# ADC.net
KiCad netlist of a schematic drawn in Altium Designer
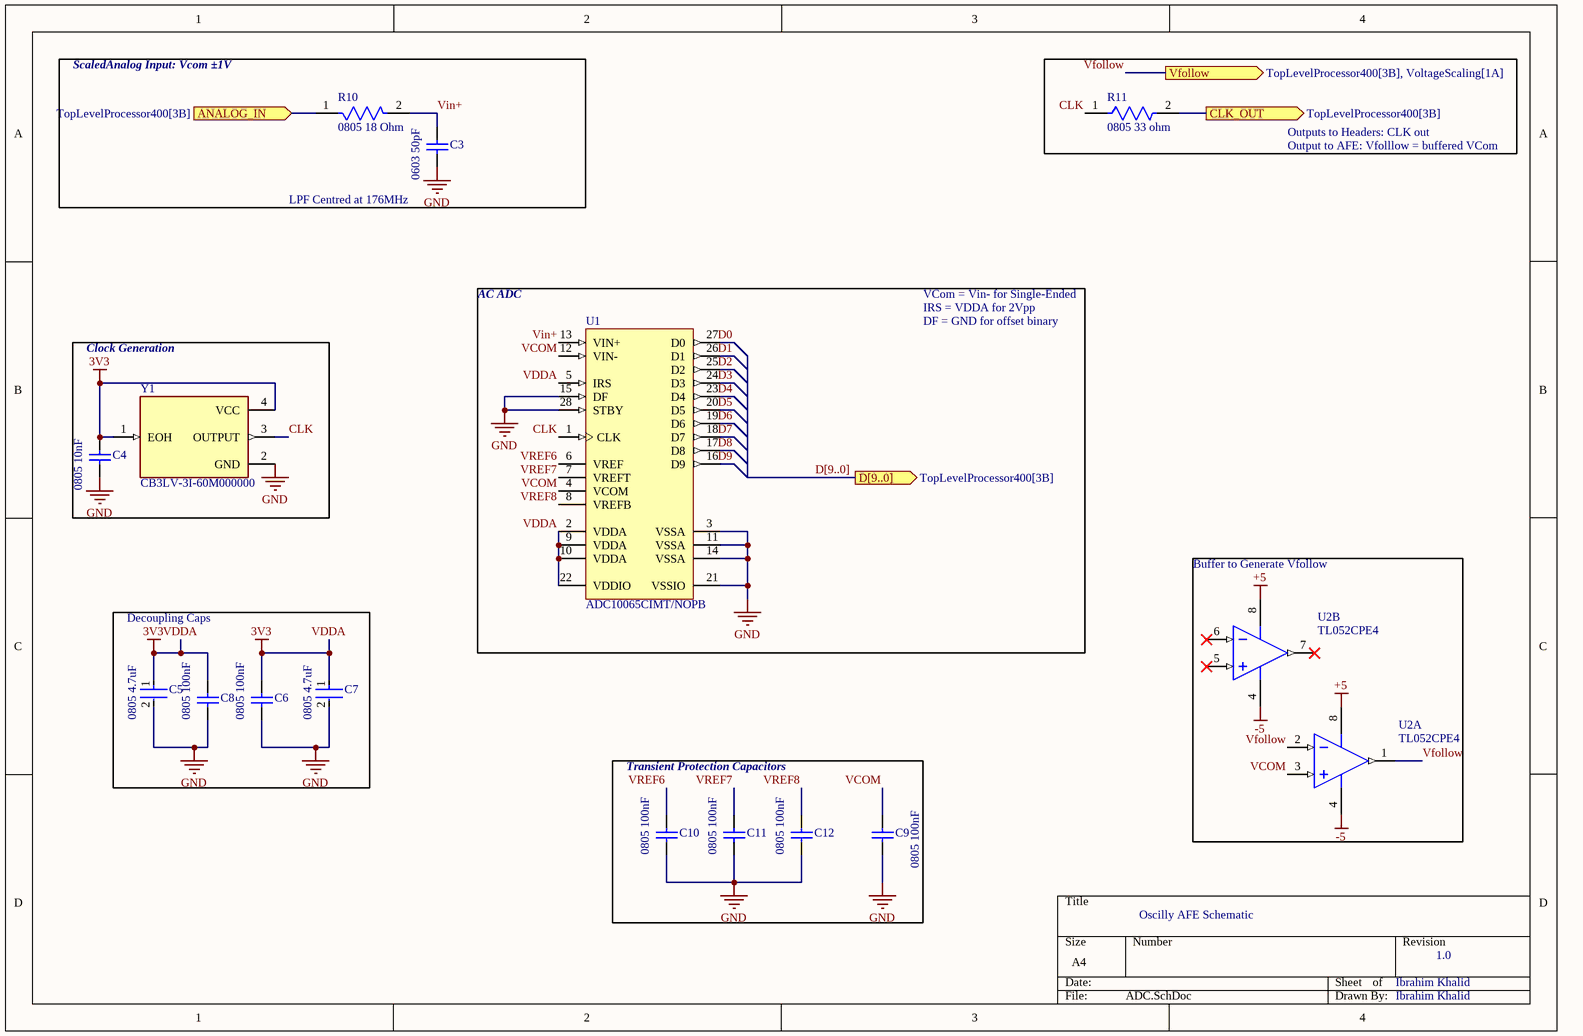
[diagram p0: ADC.SchDoc]

(export (version "E")
  (design (tool "Eeschema 10.0.6"))
  (components
    (comp (ref "C3")
      (value "0603 50pF")
      (footprint "CAPC1608X90X35ML15T15")
      (description "06035A500JAT2A")
      (fields (field (name "MANUFACTURER") "AVX Interconnect / Elco"))
      (libsource (lib "Altium Content Vault") (part "CAP"))
    )
    (comp (ref "C4")
      (value "0805 10nF")
      (footprint "CAPC0805(2012)100_M")
      (description "CAP 10nF 200V ±20% 0805 (2012 Metric) Thickness 1mm SMD")
      (fields (field (name "TOLERANCE") "Â±20%"))
      (libsource (lib "Altium Content Vault") (part "CAP"))
    )
    (comp (ref "C5")
      (value "0805 4.7uF")
      (footprint "FP-CC0805-0_85-MFG")
      (description "CAP CER 4.7UF 16V X7R 0805   CC0805KKX7R7BB475")
      (fields
        (field (name "MANUFACTURER") "Yageo")
        (field (name "OCTOPART") "https://octopart.com/cc0805kkx7r7bb475-yageo-34429188")
      )
      (libsource (lib "Altium Content Vault") (part "11868f565c42a9108669ba33697ecf6"))
    )
    (comp (ref "C6")
      (value "0805 100nF")
      (footprint "CAPC2013X140X50ML20T25")
      (description "0805DD104KAT2A")
      (fields (field (name "MANUFACTURER") "AVX Interconnect / Elco"))
      (libsource (lib "Altium Content Vault") (part "CAP"))
    )
    (comp (ref "C7")
      (value "0805 4.7uF")
      (footprint "FP-CC0805-0_85-MFG")
      (description "CAP CER 4.7UF 16V X7R 0805   CC0805KKX7R7BB475")
      (fields
        (field (name "MANUFACTURER") "Yageo")
        (field (name "OCTOPART") "https://octopart.com/cc0805kkx7r7bb475-yageo-34429188")
      )
      (libsource (lib "Altium Content Vault") (part "11868f565c42a9108669ba33697ecf6"))
    )
    (comp (ref "C8")
      (value "0805 100nF")
      (footprint "CAPC2013X140X50ML20T25")
      (description "0805DD104KAT2A")
      (fields (field (name "MANUFACTURER") "AVX Interconnect / Elco"))
      (libsource (lib "Altium Content Vault") (part "CAP"))
    )
    (comp (ref "C9")
      (value "0805 100nF")
      (footprint "CAPC2013X140X50ML20T25")
      (description "0805DD104KAT2A")
      (fields (field (name "MANUFACTURER") "AVX Interconnect / Elco"))
      (libsource (lib "Altium Content Vault") (part "CAP"))
    )
    (comp (ref "C10")
      (value "0805 100nF")
      (footprint "CAPC2013X140X50ML20T25")
      (description "0805DD104KAT2A")
      (fields (field (name "MANUFACTURER") "AVX Interconnect / Elco"))
      (libsource (lib "Altium Content Vault") (part "CAP"))
    )
    (comp (ref "C11")
      (value "0805 100nF")
      (footprint "CAPC2013X140X50ML20T25")
      (description "0805DD104KAT2A")
      (fields (field (name "MANUFACTURER") "AVX Interconnect / Elco"))
      (libsource (lib "Altium Content Vault") (part "CAP"))
    )
    (comp (ref "C12")
      (value "0805 100nF")
      (footprint "CAPC2013X140X50ML20T25")
      (description "0805DD104KAT2A")
      (fields (field (name "MANUFACTURER") "AVX Interconnect / Elco"))
      (libsource (lib "Altium Content Vault") (part "CAP"))
    )
    (comp (ref "R10")
      (value "0805 18 Ohm")
      (footprint "FP-CR0805-IPC_B")
      (description "Thick Film Chip Resistors 0805 18Ω 0.125W 5% 200ppm/°C  CR0805-JW-180ELF")
      (fields (field (name "TOLERANCE") "5%"))
      (libsource (lib "Altium Content Vault") (part "1029c3af85768c4190bb7ad29bc67b5"))
    )
    (comp (ref "R11")
      (value "0805 33 ohm")
      (footprint "FP-AC0805-MFG")
      (description "RES SMD 33 OHM 1% 1/8W 0805")
      (fields
        (field (name "OCTOPART") "https://octopart.com/ac0805fr-0733rl-yageo-46503501")
        (field (name "MANUFACTURER") "Yageo")
      )
      (libsource (lib "Altium Content Vault") (part "1029c3af85768c4190bb7ad29bc67b5"))
    )
    (comp (ref "U1")
      (value "ADC10065CIMT/NOPB")
      (footprint "PW0028A_L")
      (description "10-Bit 65 MSPS 3V A/D Converter, 28-pin TSSOP, Pb-Free")
      (fields (field (name "MANUFACTURER") "Texas Instruments"))
      (libsource (lib "Altium Content Vault") (part "CON-ADC-ADC10065CIMT"))
    )
    (comp (ref "U2")
      (value "TL052CPE4")
      (footprint "TI-P8")
      (fields (field (name "MANUFACTURER") "Texas Instruments"))
      (libsource (lib "Altium Content Vault") (part "TI-AMP-D6-2-8_D"))
    )
    (comp (ref "Y1")
      (value "CB3LV-3I-60M000000")
      (footprint "OSC_CB3LV-3I-60M000000")
      (description "60 MHz XO (Standard) HCMOS, TTL Oscillator 3.3V Enable/Disable 4-SMD, No Lead")
      (fields (field (name "MF") "CTS-Frequency Controls"))
      (libsource (lib "Ibrahim Khalid") (part "CB3LV-3I-60M000000"))
    )
  )
  (nets
    (net (code "1") (name "+5") (class "Default")
      (node (ref "U2") (pin "8") (pinfunction "VCC+_8") (pintype "power_in"))
    )
    (net (code "2") (name "-5") (class "Default")
      (node (ref "U2") (pin "4") (pinfunction "VCC-_4") (pintype "power_in"))
    )
    (net (code "3") (name "/ANALOG_IN") (class "Default")
      (node (ref "R10") (pin "1") (pinfunction "1_1") (pintype "passive"))
    )
    (net (code "4") (name "/CLK") (class "Default")
      (node (ref "R11") (pin "1") (pinfunction "1_1") (pintype "passive"))
      (node (ref "U1") (pin "1") (pinfunction "CLK_1") (pintype "input"))
      (node (ref "Y1") (pin "3") (pinfunction "OUTPUT_3") (pintype "output"))
    )
    (net (code "5") (name "/CLK_OUT") (class "Default")
      (node (ref "R11") (pin "2") (pinfunction "2_2") (pintype "passive"))
    )
    (net (code "6") (name "/D0") (class "Default")
      (node (ref "U1") (pin "27") (pinfunction "D0_27") (pintype "output"))
    )
    (net (code "7") (name "/D1") (class "Default")
      (node (ref "U1") (pin "26") (pinfunction "D1_26") (pintype "output"))
    )
    (net (code "8") (name "/D2") (class "Default")
      (node (ref "U1") (pin "25") (pinfunction "D2_25") (pintype "output"))
    )
    (net (code "9") (name "/D3") (class "Default")
      (node (ref "U1") (pin "24") (pinfunction "D3_24") (pintype "output"))
    )
    (net (code "10") (name "/D4") (class "Default")
      (node (ref "U1") (pin "23") (pinfunction "D4_23") (pintype "output"))
    )
    (net (code "11") (name "/D5") (class "Default")
      (node (ref "U1") (pin "20") (pinfunction "D5_20") (pintype "output"))
    )
    (net (code "12") (name "/D6") (class "Default")
      (node (ref "U1") (pin "19") (pinfunction "D6_19") (pintype "output"))
    )
    (net (code "13") (name "/D7") (class "Default")
      (node (ref "U1") (pin "18") (pinfunction "D7_18") (pintype "output"))
    )
    (net (code "14") (name "/D8") (class "Default")
      (node (ref "U1") (pin "17") (pinfunction "D8_17") (pintype "output"))
    )
    (net (code "15") (name "/D9") (class "Default")
      (node (ref "U1") (pin "16") (pinfunction "D9_16") (pintype "output"))
    )
    (net (code "17") (name "/VCOM") (class "Default")
      (node (ref "C9") (pin "1") (pinfunction "1_1") (pintype "passive"))
      (node (ref "U1") (pin "12") (pinfunction "VIN-_12") (pintype "input"))
      (node (ref "U1") (pin "4") (pinfunction "VCOM_4") (pintype "power_in"))
      (node (ref "U2") (pin "3") (pinfunction "IN1+_3") (pintype "input"))
    )
    (net (code "18") (name "/VREF6") (class "Default")
      (node (ref "C10") (pin "1") (pinfunction "1_1") (pintype "passive"))
      (node (ref "U1") (pin "6") (pinfunction "VREF_6") (pintype "power_in"))
    )
    (net (code "19") (name "/VREF7") (class "Default")
      (node (ref "C11") (pin "1") (pinfunction "1_1") (pintype "passive"))
      (node (ref "U1") (pin "7") (pinfunction "VREFT_7") (pintype "power_in"))
    )
    (net (code "20") (name "/VREF8") (class "Default")
      (node (ref "C12") (pin "1") (pinfunction "1_1") (pintype "passive"))
      (node (ref "U1") (pin "8") (pinfunction "VREFB_8") (pintype "power_in"))
    )
    (net (code "21") (name "/Vfollow") (class "Default")
      (node (ref "U2") (pin "1") (pinfunction "OUT1_1") (pintype "output"))
      (node (ref "U2") (pin "2") (pinfunction "IN1-_2") (pintype "input"))
    )
    (net (code "22") (name "/Vin+") (class "Default")
      (node (ref "C3") (pin "1") (pinfunction "1_1") (pintype "passive"))
      (node (ref "R10") (pin "2") (pinfunction "2_2") (pintype "passive"))
      (node (ref "U1") (pin "13") (pinfunction "VIN+_13") (pintype "input"))
    )
    (net (code "23") (name "3V3") (class "Default")
      (node (ref "C4") (pin "1") (pinfunction "1_1") (pintype "passive"))
      (node (ref "C5") (pin "1") (pinfunction "1_1") (pintype "passive"))
      (node (ref "C6") (pin "1") (pinfunction "1_1") (pintype "passive"))
      (node (ref "C7") (pin "1") (pinfunction "1_1") (pintype "passive"))
      (node (ref "C8") (pin "1") (pinfunction "1_1") (pintype "passive"))
      (node (ref "U1") (pin "10") (pinfunction "VDDA_10") (pintype "power_in"))
      (node (ref "U1") (pin "2") (pinfunction "VDDA_2") (pintype "power_in"))
      (node (ref "U1") (pin "22") (pinfunction "VDDIO_22") (pintype "power_in"))
      (node (ref "U1") (pin "5") (pinfunction "IRS_5") (pintype "input"))
      (node (ref "U1") (pin "9") (pinfunction "VDDA_9") (pintype "power_in"))
      (node (ref "Y1") (pin "1") (pinfunction "EOH_1") (pintype "input"))
      (node (ref "Y1") (pin "4") (pinfunction "VCC_4") (pintype "power_in"))
    )
    (net (code "24") (name "GND") (class "Default")
      (node (ref "C10") (pin "2") (pinfunction "2_2") (pintype "passive"))
      (node (ref "C11") (pin "2") (pinfunction "2_2") (pintype "passive"))
      (node (ref "C12") (pin "2") (pinfunction "2_2") (pintype "passive"))
      (node (ref "C3") (pin "2") (pinfunction "2_2") (pintype "passive"))
      (node (ref "C4") (pin "2") (pinfunction "2_2") (pintype "passive"))
      (node (ref "C5") (pin "2") (pinfunction "2_2") (pintype "passive"))
      (node (ref "C6") (pin "2") (pinfunction "2_2") (pintype "passive"))
      (node (ref "C7") (pin "2") (pinfunction "2_2") (pintype "passive"))
      (node (ref "C8") (pin "2") (pinfunction "2_2") (pintype "passive"))
      (node (ref "C9") (pin "2") (pinfunction "2_2") (pintype "passive"))
      (node (ref "U1") (pin "11") (pinfunction "VSSA_11") (pintype "power_in"))
      (node (ref "U1") (pin "14") (pinfunction "VSSA_14") (pintype "power_in"))
      (node (ref "U1") (pin "15") (pinfunction "DF_15") (pintype "input"))
      (node (ref "U1") (pin "21") (pinfunction "VSSIO_21") (pintype "power_in"))
      (node (ref "U1") (pin "28") (pinfunction "STBY_28") (pintype "input"))
      (node (ref "U1") (pin "3") (pinfunction "VSSA_3") (pintype "power_in"))
      (node (ref "Y1") (pin "2") (pinfunction "GND_2") (pintype "power_in"))
    )
    (net (code "25") (name "unconnected-(U2B-IN2+-Pad5)") (class "Default")
      (node (ref "U2") (pin "5") (pinfunction "IN2+_5") (pintype "input+no_connect"))
    )
    (net (code "26") (name "unconnected-(U2B-IN2--Pad6)") (class "Default")
      (node (ref "U2") (pin "6") (pinfunction "IN2-_6") (pintype "input+no_connect"))
    )
    (net (code "27") (name "unconnected-(U2B-OUT2-Pad7)") (class "Default")
      (node (ref "U2") (pin "7") (pinfunction "OUT2_7") (pintype "output+no_connect"))
    )
  )
)
